# Schema.net
KiCad netlist of a schematic drawn in EAGLE
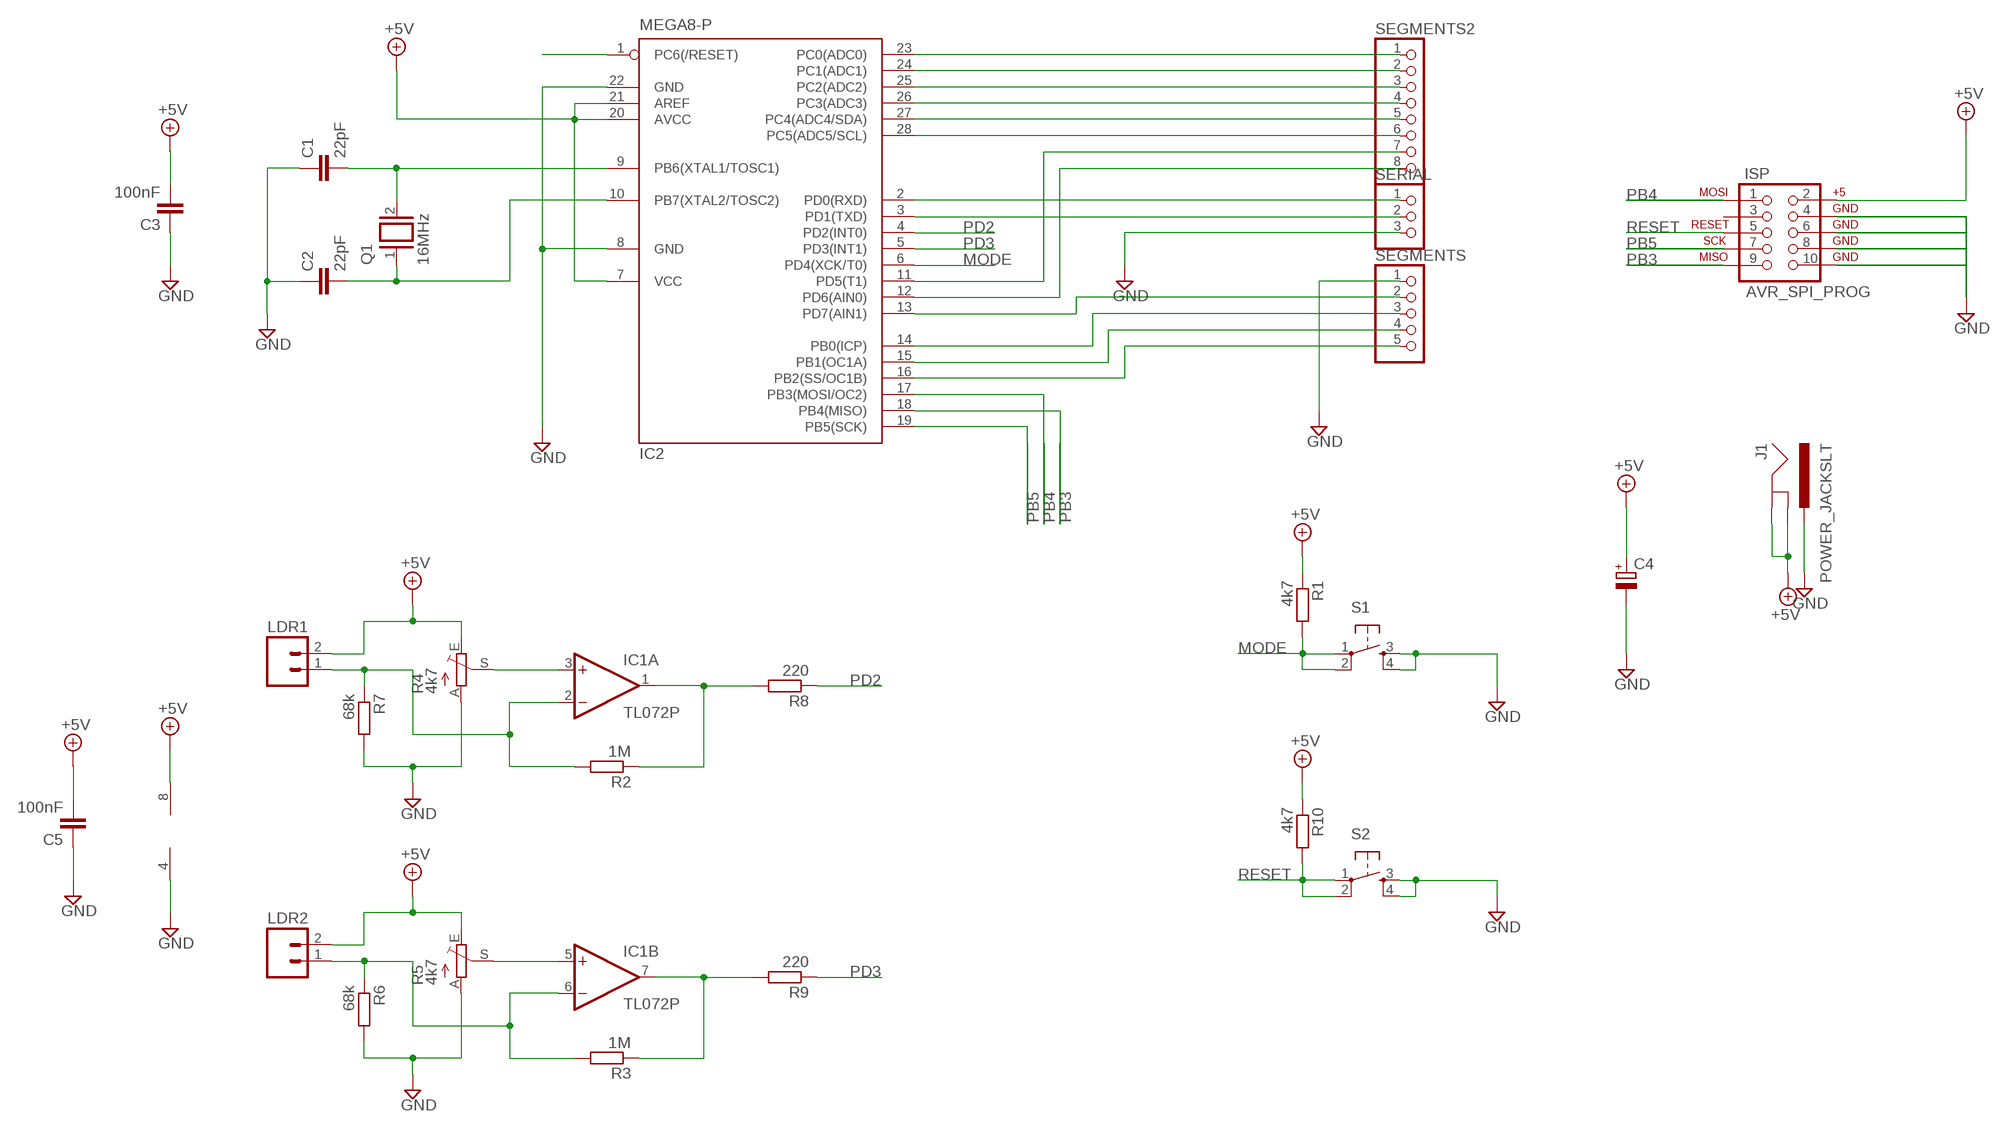
[diagram p0: schematic, sheet 1]

(export (version "E")
  (design (tool "Eeschema 10.0.6"))
  (components
    (comp (ref "C1")
      (value "22pF")
      (footprint "eagle-import:C025-024X044")
      (libsource (lib "eagle-import") (part "C-EU025-024X044"))
    )
    (comp (ref "C2")
      (value "22pF")
      (footprint "eagle-import:C025-024X044")
      (libsource (lib "eagle-import") (part "C-EU025-024X044"))
    )
    (comp (ref "C3")
      (value "100nF")
      (footprint "eagle-import:C025-024X044")
      (libsource (lib "eagle-import") (part "C-EU025-024X044"))
    )
    (comp (ref "C4")
      (value "CPOL-EUTT2D5")
      (footprint "eagle-import:TT2D5")
      (libsource (lib "eagle-import") (part "CPOL-EUTT2D5"))
    )
    (comp (ref "C5")
      (value "100nF")
      (footprint "eagle-import:C025-024X044")
      (libsource (lib "eagle-import") (part "C-EU025-024X044"))
    )
    (comp (ref "IC1")
      (value "TL072P")
      (footprint "eagle-import:DIL08")
      (libsource (lib "eagle-import") (part "TL072P"))
    )
    (comp (ref "IC2")
      (value "MEGA8-P")
      (footprint "eagle-import:DIL28-3")
      (libsource (lib "eagle-import") (part "MEGA8-P"))
    )
    (comp (ref "ISP")
      (value "AVR_SPI_PROG")
      (footprint "eagle-import:AVR_ICSP")
      (libsource (lib "eagle-import") (part "AVR_SPI_PROG"))
    )
    (comp (ref "J1")
      (value "POWER_JACKSLT")
      (footprint "eagle-import:POWER_JACK_SLOT")
      (libsource (lib "eagle-import") (part "POWER_JACKSLT"))
    )
    (comp (ref "LDR1")
      (value "M02LOCK")
      (footprint "eagle-import:1X02_LOCK")
      (libsource (lib "eagle-import") (part "M02LOCK"))
    )
    (comp (ref "LDR2")
      (value "M02LOCK")
      (footprint "eagle-import:1X02_LOCK")
      (libsource (lib "eagle-import") (part "M02LOCK"))
    )
    (comp (ref "Q1")
      (value "16MHz")
      (footprint "eagle-import:QS")
      (libsource (lib "eagle-import") (part "XTAL/S"))
    )
    (comp (ref "R1")
      (value "4k7")
      (footprint "eagle-import:0204_7")
      (libsource (lib "eagle-import") (part "R-EU_0204/7"))
    )
    (comp (ref "R2")
      (value "1M")
      (footprint "eagle-import:0204_7")
      (libsource (lib "eagle-import") (part "R-EU_0204/7"))
    )
    (comp (ref "R3")
      (value "1M")
      (footprint "eagle-import:0204_7")
      (libsource (lib "eagle-import") (part "R-EU_0204/7"))
    )
    (comp (ref "R4")
      (value "4k7")
      (footprint "eagle-import:LI10")
      (libsource (lib "eagle-import") (part "TRIM_EU-LI10"))
    )
    (comp (ref "R5")
      (value "4k7")
      (footprint "eagle-import:LI10")
      (libsource (lib "eagle-import") (part "TRIM_EU-LI10"))
    )
    (comp (ref "R6")
      (value "68k")
      (footprint "eagle-import:0204_7")
      (libsource (lib "eagle-import") (part "R-EU_0204/7"))
    )
    (comp (ref "R7")
      (value "68k")
      (footprint "eagle-import:0204_7")
      (libsource (lib "eagle-import") (part "R-EU_0204/7"))
    )
    (comp (ref "R8")
      (value "220")
      (footprint "eagle-import:0204_7")
      (libsource (lib "eagle-import") (part "R-EU_0204/7"))
    )
    (comp (ref "R9")
      (value "220")
      (footprint "eagle-import:0204_7")
      (libsource (lib "eagle-import") (part "R-EU_0204/7"))
    )
    (comp (ref "R10")
      (value "4k7")
      (footprint "eagle-import:0204_7")
      (libsource (lib "eagle-import") (part "R-EU_0204/7"))
    )
    (comp (ref "S1")
      (value "TAC_SWITCHPTH")
      (footprint "eagle-import:TACTILE-PTH")
      (libsource (lib "eagle-import") (part "TAC_SWITCHPTH"))
    )
    (comp (ref "S2")
      (value "TAC_SWITCHPTH")
      (footprint "eagle-import:TACTILE-PTH")
      (libsource (lib "eagle-import") (part "TAC_SWITCHPTH"))
    )
    (comp (ref "SEGMENTS")
      (value "PINHD-1X5")
      (footprint "eagle-import:1X05")
      (libsource (lib "eagle-import") (part "PINHD-1X5"))
    )
    (comp (ref "SEGMENTS2")
      (value "PINHD-1X8")
      (footprint "eagle-import:1X08")
      (libsource (lib "eagle-import") (part "PINHD-1X8"))
    )
    (comp (ref "SERIAL")
      (value "PINHD-1X3")
      (footprint "eagle-import:1X03")
      (libsource (lib "eagle-import") (part "PINHD-1X3"))
    )
  )
  (nets
    (net (code "1") (name "+5V") (class "Default")
      (node (ref "C3") (pin "2") (pinfunction "2_2") (pintype "passive"))
      (node (ref "C4") (pin "+") (pinfunction "+_+") (pintype "passive"))
      (node (ref "C5") (pin "2") (pinfunction "2_2") (pintype "passive"))
      (node (ref "IC1") (pin "8") (pinfunction "V+_8") (pintype "power_in"))
      (node (ref "IC2") (pin "20") (pinfunction "AVCC_20") (pintype "power_in"))
      (node (ref "IC2") (pin "21") (pinfunction "AREF_21") (pintype "passive"))
      (node (ref "IC2") (pin "7") (pinfunction "VCC_7") (pintype "power_in"))
      (node (ref "ISP") (pin "2") (pinfunction "2_2") (pintype "passive"))
      (node (ref "J1") (pin "GND@1") (pinfunction "GNDBREAK_GND@1") (pintype "bidirectional"))
      (node (ref "J1") (pin "GND@2") (pinfunction "GND_GND@2") (pintype "bidirectional"))
      (node (ref "LDR1") (pin "2") (pinfunction "2_2") (pintype "passive"))
      (node (ref "LDR2") (pin "2") (pinfunction "2_2") (pintype "passive"))
      (node (ref "R1") (pin "1") (pinfunction "1_1") (pintype "passive"))
      (node (ref "R10") (pin "1") (pinfunction "1_1") (pintype "passive"))
      (node (ref "R4") (pin "E") (pinfunction "E_E") (pintype "passive"))
      (node (ref "R5") (pin "E") (pinfunction "E_E") (pintype "passive"))
    )
    (net (code "2") (name "/MODE") (class "Default")
      (node (ref "IC2") (pin "6") (pinfunction "PD4(XCK/T0)_6") (pintype "bidirectional"))
      (node (ref "R1") (pin "2") (pinfunction "2_2") (pintype "passive"))
      (node (ref "S1") (pin "1") (pinfunction "1_1") (pintype "passive"))
      (node (ref "S1") (pin "2") (pinfunction "2_2") (pintype "passive"))
    )
    (net (code "3") (name "/PB3") (class "Default")
      (node (ref "IC2") (pin "18") (pinfunction "PB4(MISO)_18") (pintype "bidirectional"))
      (node (ref "ISP") (pin "9") (pinfunction "9_9") (pintype "passive"))
    )
    (net (code "4") (name "/PB4") (class "Default")
      (node (ref "IC2") (pin "17") (pinfunction "PB3(MOSI/OC2)_17") (pintype "bidirectional"))
      (node (ref "ISP") (pin "1") (pinfunction "1_1") (pintype "passive"))
    )
    (net (code "5") (name "/PB5") (class "Default")
      (node (ref "IC2") (pin "19") (pinfunction "PB5(SCK)_19") (pintype "bidirectional"))
      (node (ref "ISP") (pin "7") (pinfunction "7_7") (pintype "passive"))
    )
    (net (code "6") (name "/PD2") (class "Default")
      (node (ref "IC2") (pin "4") (pinfunction "PD2(INT0)_4") (pintype "bidirectional"))
      (node (ref "R8") (pin "1") (pinfunction "1_1") (pintype "passive"))
    )
    (net (code "7") (name "/PD3") (class "Default")
      (node (ref "IC2") (pin "5") (pinfunction "PD3(INT1)_5") (pintype "bidirectional"))
      (node (ref "R9") (pin "1") (pinfunction "1_1") (pintype "passive"))
    )
    (net (code "8") (name "/RESET") (class "Default")
      (node (ref "IC2") (pin "1") (pinfunction "PC6(/RESET)_1") (pintype "bidirectional"))
      (node (ref "ISP") (pin "5") (pinfunction "5_5") (pintype "passive"))
      (node (ref "R10") (pin "2") (pinfunction "2_2") (pintype "passive"))
      (node (ref "S2") (pin "1") (pinfunction "1_1") (pintype "passive"))
      (node (ref "S2") (pin "2") (pinfunction "2_2") (pintype "passive"))
    )
    (net (code "9") (name "GND") (class "Default")
      (node (ref "C1") (pin "1") (pinfunction "1_1") (pintype "passive"))
      (node (ref "C2") (pin "1") (pinfunction "1_1") (pintype "passive"))
      (node (ref "C3") (pin "1") (pinfunction "1_1") (pintype "passive"))
      (node (ref "C4") (pin "-") (pinfunction "-_-") (pintype "passive"))
      (node (ref "C5") (pin "1") (pinfunction "1_1") (pintype "passive"))
      (node (ref "IC1") (pin "4") (pinfunction "V-_4") (pintype "power_in"))
      (node (ref "IC2") (pin "22") (pinfunction "GND_22") (pintype "power_in"))
      (node (ref "IC2") (pin "8") (pinfunction "GND_8") (pintype "power_in"))
      (node (ref "ISP") (pin "10") (pinfunction "10_10") (pintype "passive"))
      (node (ref "ISP") (pin "4") (pinfunction "4_4") (pintype "passive"))
      (node (ref "ISP") (pin "6") (pinfunction "6_6") (pintype "passive"))
      (node (ref "ISP") (pin "8") (pinfunction "8_8") (pintype "passive"))
      (node (ref "J1") (pin "PWR") (pinfunction "PWR_PWR") (pintype "bidirectional"))
      (node (ref "R4") (pin "A") (pinfunction "A_A") (pintype "passive"))
      (node (ref "R5") (pin "A") (pinfunction "A_A") (pintype "passive"))
      (node (ref "R6") (pin "2") (pinfunction "2_2") (pintype "passive"))
      (node (ref "R7") (pin "2") (pinfunction "2_2") (pintype "passive"))
      (node (ref "S1") (pin "3") (pinfunction "3_3") (pintype "passive"))
      (node (ref "S1") (pin "4") (pinfunction "4_4") (pintype "passive"))
      (node (ref "S2") (pin "3") (pinfunction "3_3") (pintype "passive"))
      (node (ref "S2") (pin "4") (pinfunction "4_4") (pintype "passive"))
      (node (ref "SEGMENTS") (pin "1") (pinfunction "1_1") (pintype "passive"))
      (node (ref "SERIAL") (pin "3") (pinfunction "3_3") (pintype "passive"))
    )
    (net (code "10") (name "Net-(IC1A-+IN)") (class "Default")
      (node (ref "IC1") (pin "3") (pinfunction "+IN_3") (pintype "input"))
      (node (ref "R4") (pin "S") (pinfunction "S_S") (pintype "passive"))
    )
    (net (code "11") (name "Net-(IC1A--IN)") (class "Default")
      (node (ref "IC1") (pin "2") (pinfunction "-IN_2") (pintype "input"))
      (node (ref "LDR1") (pin "1") (pinfunction "1_1") (pintype "passive"))
      (node (ref "R2") (pin "2") (pinfunction "2_2") (pintype "passive"))
      (node (ref "R7") (pin "1") (pinfunction "1_1") (pintype "passive"))
    )
    (net (code "12") (name "Net-(IC1A-OUT)") (class "Default")
      (node (ref "IC1") (pin "1") (pinfunction "OUT_1") (pintype "output"))
      (node (ref "R2") (pin "1") (pinfunction "1_1") (pintype "passive"))
      (node (ref "R8") (pin "2") (pinfunction "2_2") (pintype "passive"))
    )
    (net (code "13") (name "Net-(IC1B-+IN)") (class "Default")
      (node (ref "IC1") (pin "5") (pinfunction "+IN_5") (pintype "input"))
      (node (ref "R5") (pin "S") (pinfunction "S_S") (pintype "passive"))
    )
    (net (code "14") (name "Net-(IC1B--IN)") (class "Default")
      (node (ref "IC1") (pin "6") (pinfunction "-IN_6") (pintype "input"))
      (node (ref "LDR2") (pin "1") (pinfunction "1_1") (pintype "passive"))
      (node (ref "R3") (pin "2") (pinfunction "2_2") (pintype "passive"))
      (node (ref "R6") (pin "1") (pinfunction "1_1") (pintype "passive"))
    )
    (net (code "15") (name "Net-(IC1B-OUT)") (class "Default")
      (node (ref "IC1") (pin "7") (pinfunction "OUT_7") (pintype "output"))
      (node (ref "R3") (pin "1") (pinfunction "1_1") (pintype "passive"))
      (node (ref "R9") (pin "2") (pinfunction "2_2") (pintype "passive"))
    )
    (net (code "16") (name "Net-(IC2-PB0(ICP))") (class "Default")
      (node (ref "IC2") (pin "14") (pinfunction "PB0(ICP)_14") (pintype "bidirectional"))
      (node (ref "SEGMENTS") (pin "3") (pinfunction "3_3") (pintype "passive"))
    )
    (net (code "17") (name "Net-(IC2-PB1(OC1A))") (class "Default")
      (node (ref "IC2") (pin "15") (pinfunction "PB1(OC1A)_15") (pintype "bidirectional"))
      (node (ref "SEGMENTS") (pin "4") (pinfunction "4_4") (pintype "passive"))
    )
    (net (code "18") (name "Net-(IC2-PB2(SS{slash}OC1B))") (class "Default")
      (node (ref "IC2") (pin "16") (pinfunction "PB2(SS/OC1B)_16") (pintype "bidirectional"))
      (node (ref "SEGMENTS") (pin "5") (pinfunction "5_5") (pintype "passive"))
    )
    (net (code "19") (name "Net-(IC2-PB6(XTAL1{slash}TOSC1))") (class "Default")
      (node (ref "C1") (pin "2") (pinfunction "2_2") (pintype "passive"))
      (node (ref "IC2") (pin "9") (pinfunction "PB6(XTAL1/TOSC1)_9") (pintype "bidirectional"))
      (node (ref "Q1") (pin "2") (pinfunction "2_2") (pintype "passive"))
    )
    (net (code "20") (name "Net-(IC2-PB7(XTAL2{slash}TOSC2))") (class "Default")
      (node (ref "C2") (pin "2") (pinfunction "2_2") (pintype "passive"))
      (node (ref "IC2") (pin "10") (pinfunction "PB7(XTAL2/TOSC2)_10") (pintype "bidirectional"))
      (node (ref "Q1") (pin "1") (pinfunction "1_1") (pintype "passive"))
    )
    (net (code "21") (name "Net-(IC2-PC0(ADC0))") (class "Default")
      (node (ref "IC2") (pin "23") (pinfunction "PC0(ADC0)_23") (pintype "bidirectional"))
      (node (ref "SEGMENTS2") (pin "1") (pinfunction "1_1") (pintype "passive"))
    )
    (net (code "22") (name "Net-(IC2-PC1(ADC1))") (class "Default")
      (node (ref "IC2") (pin "24") (pinfunction "PC1(ADC1)_24") (pintype "bidirectional"))
      (node (ref "SEGMENTS2") (pin "2") (pinfunction "2_2") (pintype "passive"))
    )
    (net (code "23") (name "Net-(IC2-PC2(ADC2))") (class "Default")
      (node (ref "IC2") (pin "25") (pinfunction "PC2(ADC2)_25") (pintype "bidirectional"))
      (node (ref "SEGMENTS2") (pin "3") (pinfunction "3_3") (pintype "passive"))
    )
    (net (code "24") (name "Net-(IC2-PC3(ADC3))") (class "Default")
      (node (ref "IC2") (pin "26") (pinfunction "PC3(ADC3)_26") (pintype "bidirectional"))
      (node (ref "SEGMENTS2") (pin "4") (pinfunction "4_4") (pintype "passive"))
    )
    (net (code "25") (name "Net-(IC2-PC4(ADC4{slash}SDA))") (class "Default")
      (node (ref "IC2") (pin "27") (pinfunction "PC4(ADC4/SDA)_27") (pintype "bidirectional"))
      (node (ref "SEGMENTS2") (pin "5") (pinfunction "5_5") (pintype "passive"))
    )
    (net (code "26") (name "Net-(IC2-PC5(ADC5{slash}SCL))") (class "Default")
      (node (ref "IC2") (pin "28") (pinfunction "PC5(ADC5/SCL)_28") (pintype "bidirectional"))
      (node (ref "SEGMENTS2") (pin "6") (pinfunction "6_6") (pintype "passive"))
    )
    (net (code "27") (name "Net-(IC2-PD0(RXD))") (class "Default")
      (node (ref "IC2") (pin "2") (pinfunction "PD0(RXD)_2") (pintype "bidirectional"))
      (node (ref "SERIAL") (pin "1") (pinfunction "1_1") (pintype "passive"))
    )
    (net (code "28") (name "Net-(IC2-PD1(TXD))") (class "Default")
      (node (ref "IC2") (pin "3") (pinfunction "PD1(TXD)_3") (pintype "bidirectional"))
      (node (ref "SERIAL") (pin "2") (pinfunction "2_2") (pintype "passive"))
    )
    (net (code "29") (name "Net-(IC2-PD5(T1))") (class "Default")
      (node (ref "IC2") (pin "11") (pinfunction "PD5(T1)_11") (pintype "bidirectional"))
      (node (ref "SEGMENTS2") (pin "7") (pinfunction "7_7") (pintype "passive"))
    )
    (net (code "30") (name "Net-(IC2-PD6(AIN0))") (class "Default")
      (node (ref "IC2") (pin "12") (pinfunction "PD6(AIN0)_12") (pintype "bidirectional"))
      (node (ref "SEGMENTS2") (pin "8") (pinfunction "8_8") (pintype "passive"))
    )
    (net (code "31") (name "Net-(IC2-PD7(AIN1))") (class "Default")
      (node (ref "IC2") (pin "13") (pinfunction "PD7(AIN1)_13") (pintype "bidirectional"))
      (node (ref "SEGMENTS") (pin "2") (pinfunction "2_2") (pintype "passive"))
    )
    (net (code "32") (name "unconnected-(ISP-Pad3)") (class "Default")
      (node (ref "ISP") (pin "3") (pinfunction "3_3") (pintype "passive"))
    )
  )
)
